# Castle_2_2_2_060623.net
KiCad netlist of a schematic drawn in EAGLE
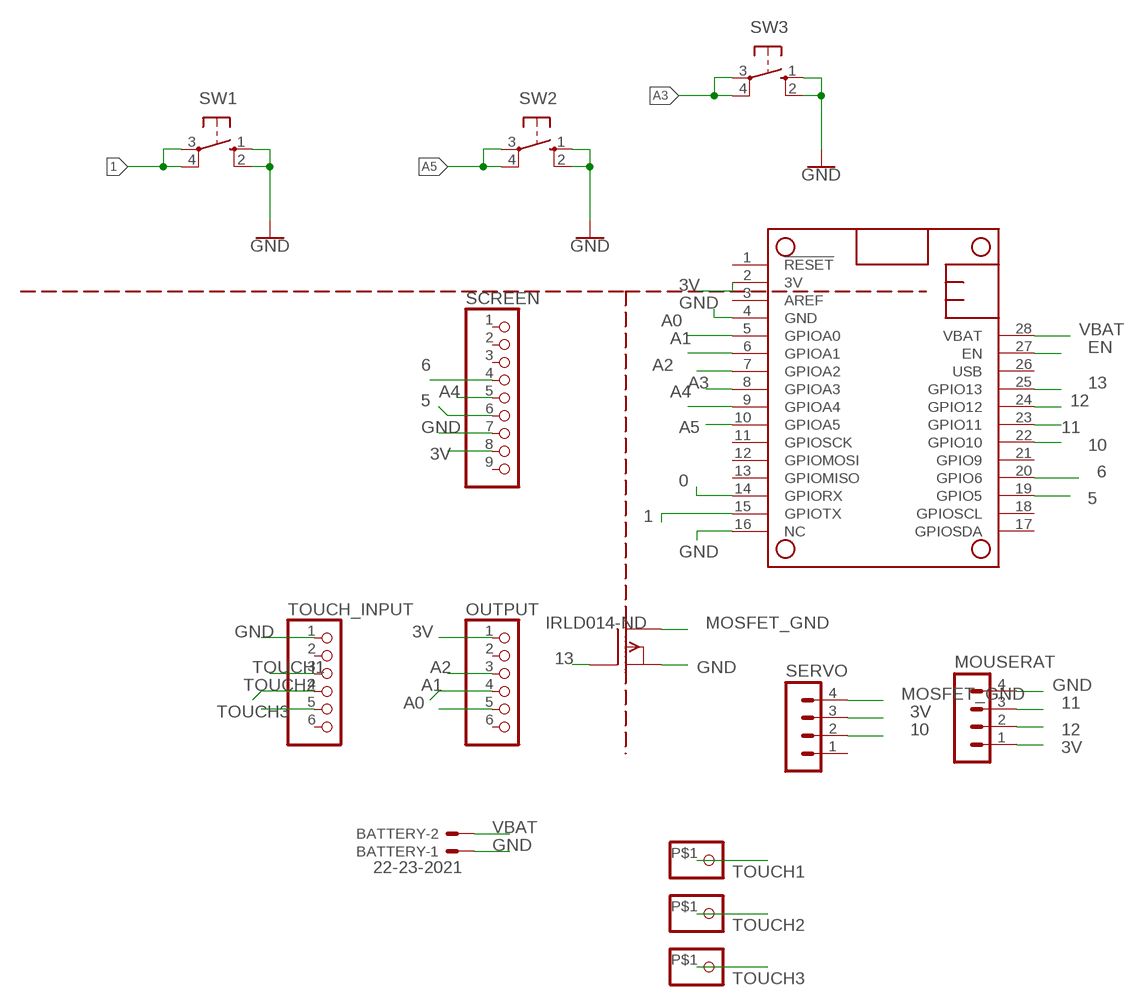
[diagram p0: schematic, sheet 1]

(export (version "E")
  (design (tool "Eeschema 10.0.6"))
  (components
    (comp (ref "BATTERY")
      (value "22-23-2021")
      (footprint "eagle-import:22-23-2021")
      (fields (field (name "MF") "MOLEX"))
      (libsource (lib "eagle-import") (part "22-23-2021"))
    )
    (comp (ref "EXTRAGND")
      (value "PINHD-1X1-BIGPOGO")
      (footprint "eagle-import:1X1-BIGPOGO")
      (libsource (lib "eagle-import") (part "PINHD-1X1-BIGPOGO"))
    )
    (comp (ref "EXTRAGND1")
      (value "PINHD-1X1-BIGPOGO")
      (footprint "eagle-import:1X1-BIGPOGO")
      (libsource (lib "eagle-import") (part "PINHD-1X1-BIGPOGO"))
    )
    (comp (ref "EXTRAGND2")
      (value "PINHD-1X1-BIGPOGO")
      (footprint "eagle-import:1X1-BIGPOGO")
      (libsource (lib "eagle-import") (part "PINHD-1X1-BIGPOGO"))
    )
    (comp (ref "IRLD014-ND")
      (value "IRFD9210")
      (footprint "eagle-import:DIL04")
      (libsource (lib "eagle-import") (part "IRFD9210"))
    )
    (comp (ref "MOUSERAT")
      (value "MA04-1")
      (footprint "eagle-import:MA04-1")
      (libsource (lib "eagle-import") (part "MA04-1"))
    )
    (comp (ref "MS2")
      (value "FEATHERWING_NODIM")
      (footprint "eagle-import:FEATHERWING_DIM")
      (libsource (lib "eagle-import") (part "FEATHERWING_NODIM"))
    )
    (comp (ref "OUTPUT")
      (value "PINHD-1X6")
      (footprint "eagle-import:1X06")
      (libsource (lib "eagle-import") (part "PINHD-1X6"))
    )
    (comp (ref "SCREEN")
      (value "PINHD-1X9")
      (footprint "eagle-import:1X09-BIG")
      (libsource (lib "eagle-import") (part "PINHD-1X9"))
    )
    (comp (ref "SERVO")
      (value "MA04-1")
      (footprint "eagle-import:MA04-1")
      (libsource (lib "eagle-import") (part "MA04-1"))
    )
    (comp (ref "SW1")
      (value "10-XX")
      (footprint "eagle-import:B3F-10XX")
      (libsource (lib "eagle-import") (part "10-XX"))
    )
    (comp (ref "SW2")
      (value "10-XX")
      (footprint "eagle-import:B3F-10XX")
      (libsource (lib "eagle-import") (part "10-XX"))
    )
    (comp (ref "SW3")
      (value "10-XX")
      (footprint "eagle-import:B3F-10XX")
      (libsource (lib "eagle-import") (part "10-XX"))
    )
    (comp (ref "TOUCH_INPUT")
      (value "PINHD-1X6")
      (footprint "eagle-import:1X06")
      (libsource (lib "eagle-import") (part "PINHD-1X6"))
    )
  )
  (nets
    (net (code "1") (name "/0") (class "Default")
      (node (ref "MS2") (pin "14") (pinfunction "GPIORX_14") (pintype "bidirectional"))
    )
    (net (code "2") (name "/3V") (class "Default")
      (node (ref "MOUSERAT") (pin "1") (pinfunction "1_1") (pintype "passive"))
      (node (ref "MS2") (pin "2") (pinfunction "3V_2") (pintype "power_in"))
      (node (ref "OUTPUT") (pin "1") (pinfunction "1_1") (pintype "passive"))
      (node (ref "SCREEN") (pin "8") (pinfunction "8_8") (pintype "passive"))
      (node (ref "SERVO") (pin "3") (pinfunction "3_3") (pintype "passive"))
    )
    (net (code "3") (name "/5") (class "Default")
      (node (ref "MS2") (pin "19") (pinfunction "GPIO5_19") (pintype "bidirectional"))
      (node (ref "SCREEN") (pin "6") (pinfunction "6_6") (pintype "passive"))
    )
    (net (code "4") (name "/6") (class "Default")
      (node (ref "MS2") (pin "20") (pinfunction "GPIO6_20") (pintype "bidirectional"))
      (node (ref "SCREEN") (pin "4") (pinfunction "4_4") (pintype "passive"))
    )
    (net (code "5") (name "/10") (class "Default")
      (node (ref "MS2") (pin "22") (pinfunction "GPIO10_22") (pintype "bidirectional"))
      (node (ref "SERVO") (pin "2") (pinfunction "2_2") (pintype "passive"))
    )
    (net (code "6") (name "/11") (class "Default")
      (node (ref "MOUSERAT") (pin "3") (pinfunction "3_3") (pintype "passive"))
      (node (ref "MS2") (pin "23") (pinfunction "GPIO11_23") (pintype "bidirectional"))
    )
    (net (code "7") (name "/12") (class "Default")
      (node (ref "MOUSERAT") (pin "2") (pinfunction "2_2") (pintype "passive"))
      (node (ref "MS2") (pin "24") (pinfunction "GPIO12_24") (pintype "bidirectional"))
    )
    (net (code "8") (name "/13") (class "Default")
      (node (ref "IRLD014-ND") (pin "1") (pinfunction "G_1") (pintype "passive"))
      (node (ref "MS2") (pin "25") (pinfunction "GPIO13_25") (pintype "bidirectional"))
    )
    (net (code "9") (name "/A0") (class "Default")
      (node (ref "MS2") (pin "5") (pinfunction "GPIOA0_5") (pintype "bidirectional"))
      (node (ref "OUTPUT") (pin "5") (pinfunction "5_5") (pintype "passive"))
    )
    (net (code "10") (name "/A1") (class "Default")
      (node (ref "MS2") (pin "6") (pinfunction "GPIOA1_6") (pintype "bidirectional"))
      (node (ref "OUTPUT") (pin "4") (pinfunction "4_4") (pintype "passive"))
    )
    (net (code "11") (name "/A2") (class "Default")
      (node (ref "MS2") (pin "7") (pinfunction "GPIOA2_7") (pintype "bidirectional"))
      (node (ref "OUTPUT") (pin "3") (pinfunction "3_3") (pintype "passive"))
    )
    (net (code "12") (name "/A4") (class "Default")
      (node (ref "MS2") (pin "9") (pinfunction "GPIOA4_9") (pintype "bidirectional"))
      (node (ref "SCREEN") (pin "5") (pinfunction "5_5") (pintype "passive"))
    )
    (net (code "13") (name "/EN") (class "Default")
      (node (ref "MS2") (pin "27") (pinfunction "EN_27") (pintype "passive"))
    )
    (net (code "14") (name "/MOSFET_GND") (class "Default")
      (node (ref "IRLD014-ND") (pin "3") (pinfunction "D_3") (pintype "passive"))
      (node (ref "IRLD014-ND") (pin "4") (pinfunction "D_4") (pintype "passive"))
      (node (ref "SERVO") (pin "4") (pinfunction "4_4") (pintype "passive"))
    )
    (net (code "15") (name "/TOUCH1") (class "Default")
      (node (ref "EXTRAGND") (pin "P$1") (pinfunction "1_P$1") (pintype "passive"))
      (node (ref "TOUCH_INPUT") (pin "3") (pinfunction "3_3") (pintype "passive"))
    )
    (net (code "16") (name "/TOUCH2") (class "Default")
      (node (ref "EXTRAGND1") (pin "P$1") (pinfunction "1_P$1") (pintype "passive"))
      (node (ref "TOUCH_INPUT") (pin "4") (pinfunction "4_4") (pintype "passive"))
    )
    (net (code "17") (name "/TOUCH3") (class "Default")
      (node (ref "EXTRAGND2") (pin "P$1") (pinfunction "1_P$1") (pintype "passive"))
      (node (ref "TOUCH_INPUT") (pin "5") (pinfunction "5_5") (pintype "passive"))
    )
    (net (code "18") (name "/USB") (class "Default")
      (node (ref "MS2") (pin "26") (pinfunction "USB_26") (pintype "power_in"))
    )
    (net (code "19") (name "/VBAT") (class "Default")
      (node (ref "BATTERY") (pin "2") (pinfunction "S_2") (pintype "passive"))
      (node (ref "MS2") (pin "28") (pinfunction "VBAT_28") (pintype "power_in"))
    )
    (net (code "20") (name "1") (class "Default")
      (node (ref "MS2") (pin "15") (pinfunction "GPIOTX_15") (pintype "bidirectional"))
      (node (ref "SW1") (pin "3") (pinfunction "P_3") (pintype "passive"))
      (node (ref "SW1") (pin "4") (pinfunction "P1_4") (pintype "passive"))
    )
    (net (code "21") (name "A3") (class "Default")
      (node (ref "MS2") (pin "8") (pinfunction "GPIOA3_8") (pintype "bidirectional"))
      (node (ref "SW3") (pin "3") (pinfunction "P_3") (pintype "passive"))
      (node (ref "SW3") (pin "4") (pinfunction "P1_4") (pintype "passive"))
    )
    (net (code "22") (name "A5") (class "Default")
      (node (ref "MS2") (pin "10") (pinfunction "GPIOA5_10") (pintype "bidirectional"))
      (node (ref "SW2") (pin "3") (pinfunction "P_3") (pintype "passive"))
      (node (ref "SW2") (pin "4") (pinfunction "P1_4") (pintype "passive"))
    )
    (net (code "23") (name "GND") (class "Default")
      (node (ref "BATTERY") (pin "1") (pinfunction "S_1") (pintype "passive"))
      (node (ref "IRLD014-ND") (pin "2") (pinfunction "S_2") (pintype "passive"))
      (node (ref "MOUSERAT") (pin "4") (pinfunction "4_4") (pintype "passive"))
      (node (ref "MS2") (pin "16") (pinfunction "NC_16") (pintype "passive"))
      (node (ref "MS2") (pin "4") (pinfunction "GND_4") (pintype "power_in"))
      (node (ref "SCREEN") (pin "7") (pinfunction "7_7") (pintype "passive"))
      (node (ref "SW1") (pin "1") (pinfunction "S_1") (pintype "passive"))
      (node (ref "SW1") (pin "2") (pinfunction "S1_2") (pintype "passive"))
      (node (ref "SW2") (pin "1") (pinfunction "S_1") (pintype "passive"))
      (node (ref "SW2") (pin "2") (pinfunction "S1_2") (pintype "passive"))
      (node (ref "SW3") (pin "1") (pinfunction "S_1") (pintype "passive"))
      (node (ref "SW3") (pin "2") (pinfunction "S1_2") (pintype "passive"))
      (node (ref "TOUCH_INPUT") (pin "1") (pinfunction "1_1") (pintype "passive"))
    )
    (net (code "24") (name "unconnected-(MS2-AREF-Pad3)") (class "Default")
      (node (ref "MS2") (pin "3") (pinfunction "AREF_3") (pintype "passive"))
    )
    (net (code "25") (name "unconnected-(MS2-GPIO9-Pad21)") (class "Default")
      (node (ref "MS2") (pin "21") (pinfunction "GPIO9_21") (pintype "bidirectional"))
    )
    (net (code "26") (name "unconnected-(MS2-GPIOMISO-Pad13)") (class "Default")
      (node (ref "MS2") (pin "13") (pinfunction "GPIOMISO_13") (pintype "bidirectional"))
    )
    (net (code "27") (name "unconnected-(MS2-GPIOMOSI-Pad12)") (class "Default")
      (node (ref "MS2") (pin "12") (pinfunction "GPIOMOSI_12") (pintype "bidirectional"))
    )
    (net (code "28") (name "unconnected-(MS2-GPIOSCK-Pad11)") (class "Default")
      (node (ref "MS2") (pin "11") (pinfunction "GPIOSCK_11") (pintype "bidirectional"))
    )
    (net (code "29") (name "unconnected-(MS2-GPIOSCL-Pad18)") (class "Default")
      (node (ref "MS2") (pin "18") (pinfunction "GPIOSCL_18") (pintype "bidirectional"))
    )
    (net (code "30") (name "unconnected-(MS2-GPIOSDA-Pad17)") (class "Default")
      (node (ref "MS2") (pin "17") (pinfunction "GPIOSDA_17") (pintype "bidirectional"))
    )
    (net (code "31") (name "unconnected-(MS2-~{RESET}-Pad1)") (class "Default")
      (node (ref "MS2") (pin "1") (pinfunction "~{RESET}_1") (pintype "input"))
    )
    (net (code "32") (name "unconnected-(OUTPUT-Pad2)") (class "Default")
      (node (ref "OUTPUT") (pin "2") (pinfunction "2_2") (pintype "passive"))
    )
    (net (code "33") (name "unconnected-(OUTPUT-Pad6)") (class "Default")
      (node (ref "OUTPUT") (pin "6") (pinfunction "6_6") (pintype "passive"))
    )
    (net (code "34") (name "unconnected-(SCREEN-Pad1)") (class "Default")
      (node (ref "SCREEN") (pin "1") (pinfunction "1_1") (pintype "passive"))
    )
    (net (code "35") (name "unconnected-(SCREEN-Pad2)") (class "Default")
      (node (ref "SCREEN") (pin "2") (pinfunction "2_2") (pintype "passive"))
    )
    (net (code "36") (name "unconnected-(SCREEN-Pad3)") (class "Default")
      (node (ref "SCREEN") (pin "3") (pinfunction "3_3") (pintype "passive"))
    )
    (net (code "37") (name "unconnected-(SCREEN-Pad9)") (class "Default")
      (node (ref "SCREEN") (pin "9") (pinfunction "9_9") (pintype "passive"))
    )
    (net (code "38") (name "unconnected-(SERVO-Pad1)") (class "Default")
      (node (ref "SERVO") (pin "1") (pinfunction "1_1") (pintype "passive"))
    )
    (net (code "39") (name "unconnected-(TOUCH_INPUT-Pad2)") (class "Default")
      (node (ref "TOUCH_INPUT") (pin "2") (pinfunction "2_2") (pintype "passive"))
    )
    (net (code "40") (name "unconnected-(TOUCH_INPUT-Pad6)") (class "Default")
      (node (ref "TOUCH_INPUT") (pin "6") (pinfunction "6_6") (pintype "passive"))
    )
  )
)
